# M1_DRV8301_driver.net
KiCad netlist of a schematic drawn in Altium Designer
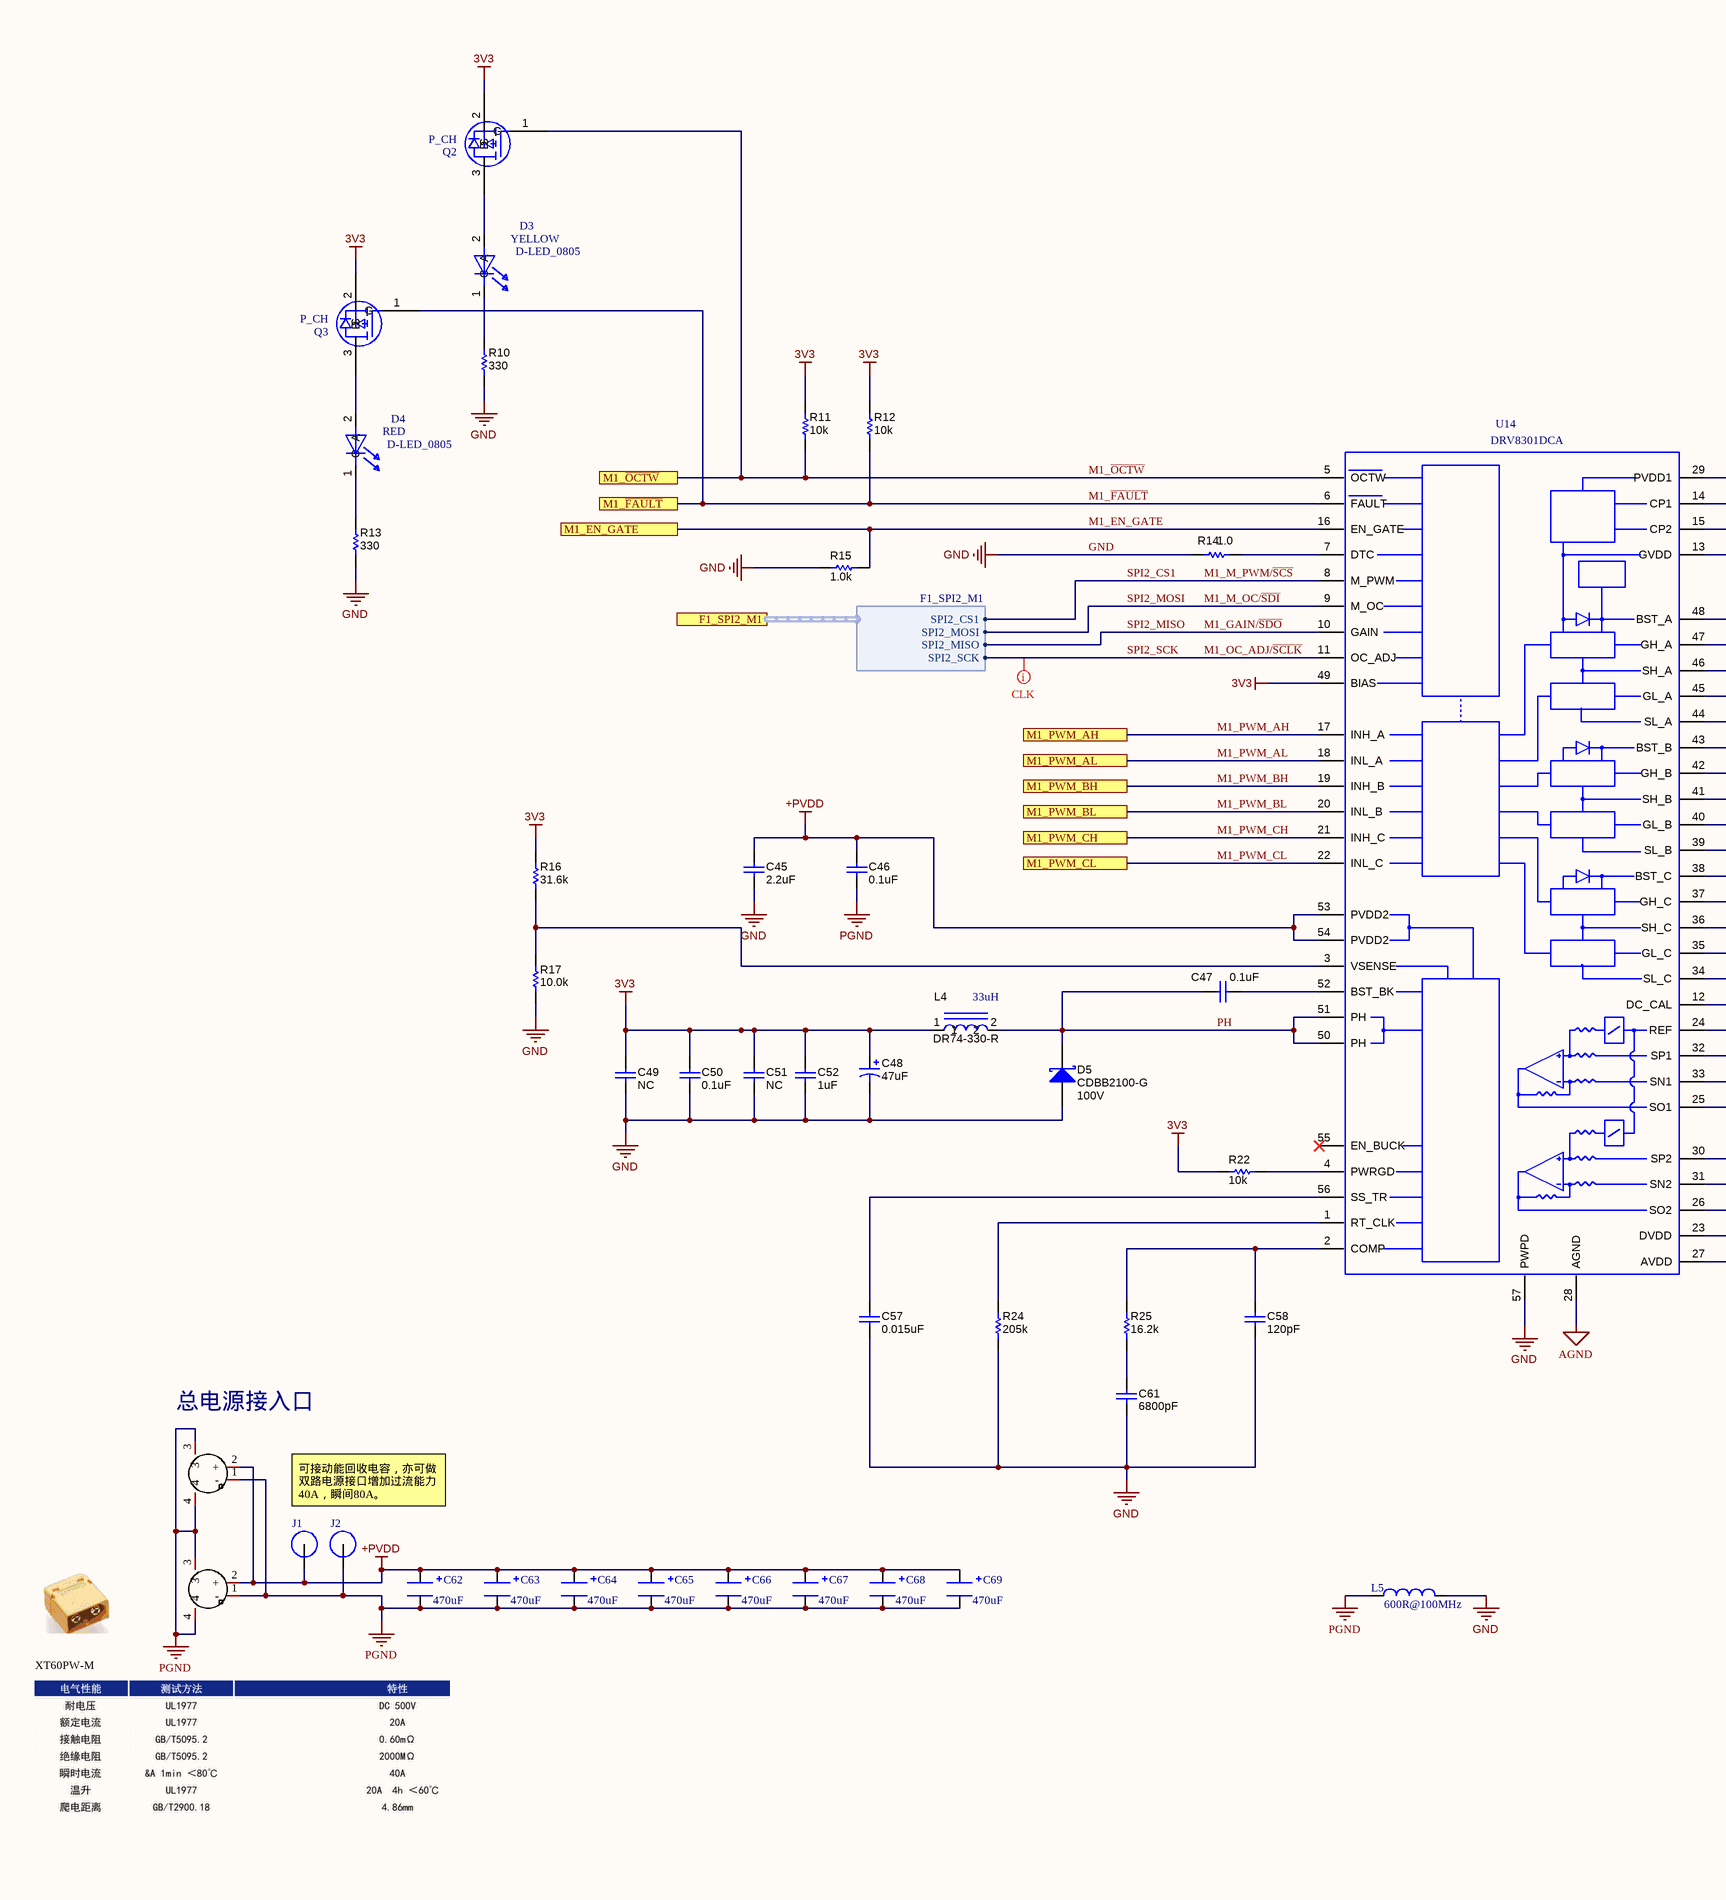
[diagram p0: M1_DRV8301_driver.SchDoc, left]
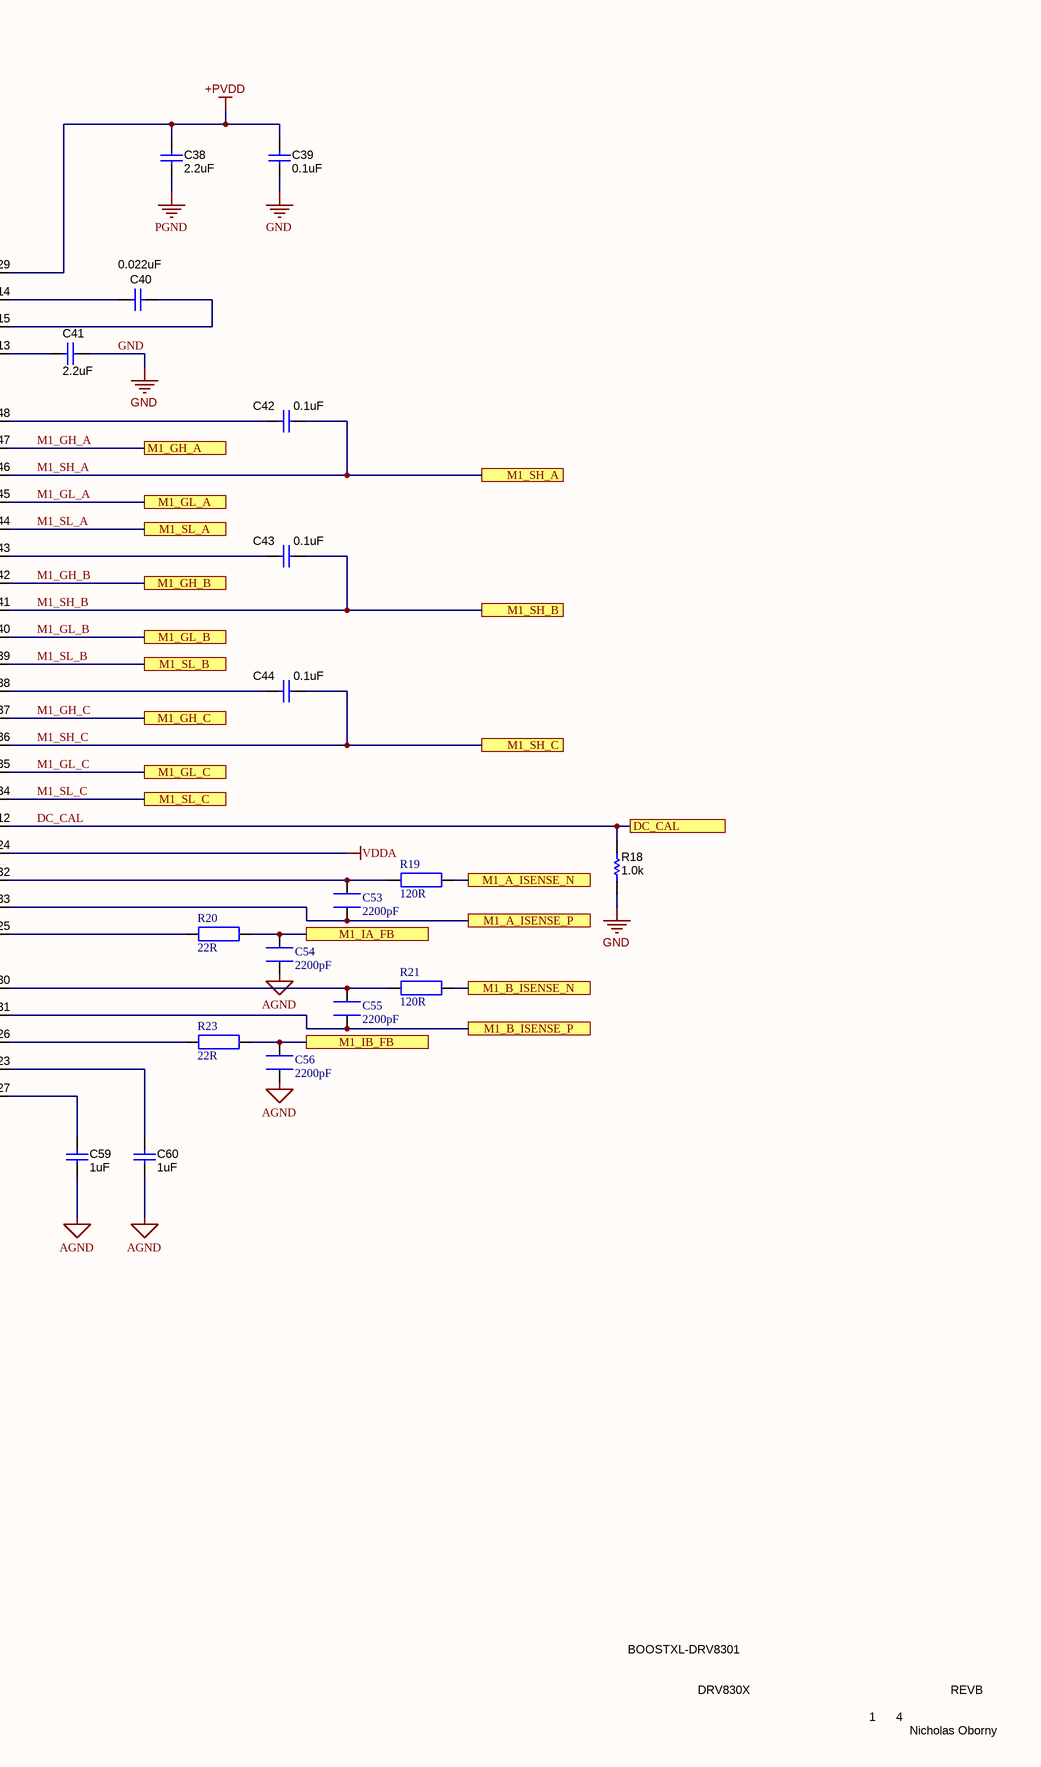
[diagram p1: M1_DRV8301_driver.SchDoc, right]

(export (version "E")
  (design (tool "Eeschema 10.0.6"))
  (components
    (comp (ref "C38")
      (value "GRM32ER72A225KA35L")
      (footprint "1210L")
      (description "CAP, CERM, 2.2uF, 100V, +/-10%, X7R, 1210")
      (fields
        (field (name "VALUEDISPLAYED") "2.2uF")
        (field (name "MANUFACTURER") "MuRata")
        (field (name "PUBLISHER") "Texas Instruments")
      )
      (libsource (lib "Capacitor_Ceramic") (part "GRM32ER72A225KA35L"))
    )
    (comp (ref "C39")
      (value "GRM188R72A104KA35D")
      (footprint "0603L")
      (description "CAP, CERM, 0.1uF, 100V, +/-10%, X7R, 0603")
      (fields
        (field (name "VALUEDISPLAYED") "0.1uF")
        (field (name "MANUFACTURER") "MuRata")
        (field (name "PUBLISHER") "Texas Instruments")
      )
      (libsource (lib "Capacitor_Ceramic") (part "GRM188R72A104KA35D"))
    )
    (comp (ref "C40")
      (value "C1608X7R1H223K")
      (footprint "0603L")
      (description "CAP, CERM, 0.022uF, 50V, +/-10%, X7R, 0603")
      (fields
        (field (name "VALUEDISPLAYED") "0.022uF")
        (field (name "MANUFACTURER") "TDK")
        (field (name "PUBLISHER") "Texas Instruments")
      )
      (libsource (lib "Capacitor_Ceramic") (part "C1608X7R1H223K"))
    )
    (comp (ref "C41")
      (value "GRM219R61E225KA12D")
      (footprint "0805L")
      (description "CAP, CERM, 2.2uF, 25V, +/-10%, X5R, 0805")
      (fields
        (field (name "VALUEDISPLAYED") "2.2uF")
        (field (name "MANUFACTURER") "MuRata")
        (field (name "PUBLISHER") "Texas Instruments")
      )
      (libsource (lib "Capacitor_Ceramic") (part "GRM219R61E225KA12D"))
    )
    (comp (ref "C42")
      (value "C1608X7R1H104K")
      (footprint "0603L")
      (description "CAP, CERM, 0.1uF, 50V, +/-10%, X7R, 0603")
      (fields
        (field (name "VALUEDISPLAYED") "0.1uF")
        (field (name "MANUFACTURER") "TDK")
        (field (name "PUBLISHER") "Texas Instruments")
      )
      (libsource (lib "Capacitor_Ceramic") (part "C1608X7R1H104K"))
    )
    (comp (ref "C43")
      (value "C1608X7R1H104K")
      (footprint "0603L")
      (description "CAP, CERM, 0.1uF, 50V, +/-10%, X7R, 0603")
      (fields
        (field (name "VALUEDISPLAYED") "0.1uF")
        (field (name "MANUFACTURER") "TDK")
        (field (name "PUBLISHER") "Texas Instruments")
      )
      (libsource (lib "Capacitor_Ceramic") (part "C1608X7R1H104K"))
    )
    (comp (ref "C44")
      (value "C1608X7R1H104K")
      (footprint "0603L")
      (description "CAP, CERM, 0.1uF, 50V, +/-10%, X7R, 0603")
      (fields
        (field (name "VALUEDISPLAYED") "0.1uF")
        (field (name "MANUFACTURER") "TDK")
        (field (name "PUBLISHER") "Texas Instruments")
      )
      (libsource (lib "Capacitor_Ceramic") (part "C1608X7R1H104K"))
    )
    (comp (ref "C45")
      (value "GRM32ER72A225KA35L")
      (footprint "1210L")
      (description "CAP, CERM, 2.2uF, 100V, +/-10%, X7R, 1210")
      (fields
        (field (name "VALUEDISPLAYED") "2.2uF")
        (field (name "MANUFACTURER") "MuRata")
        (field (name "PUBLISHER") "Texas Instruments")
      )
      (libsource (lib "Capacitor_Ceramic") (part "GRM32ER72A225KA35L"))
    )
    (comp (ref "C46")
      (value "GRM188R72A104KA35D")
      (footprint "0603L")
      (description "CAP, CERM, 0.1uF, 100V, +/-10%, X7R, 0603")
      (fields
        (field (name "VALUEDISPLAYED") "0.1uF")
        (field (name "MANUFACTURER") "MuRata")
        (field (name "PUBLISHER") "Texas Instruments")
      )
      (libsource (lib "Capacitor_Ceramic") (part "GRM188R72A104KA35D"))
    )
    (comp (ref "C47")
      (value "C1608X7R1H104K")
      (footprint "0603L")
      (description "CAP, CERM, 0.1uF, 50V, +/-10%, X7R, 0603")
      (fields
        (field (name "VALUEDISPLAYED") "0.1uF")
        (field (name "MANUFACTURER") "TDK")
        (field (name "PUBLISHER") "Texas Instruments")
      )
      (libsource (lib "Capacitor_Ceramic") (part "C1608X7R1H104K"))
    )
    (comp (ref "C48")
      (value "EEE-FK1E470P")
      (footprint "SM_RADIAL_D")
      (description "CAP, AL, 47uF, 25V, +/-20%, 0.36 ohm, SMD")
      (fields
        (field (name "VALUEDISPLAYED") "47uF")
        (field (name "MANUFACTURER") "Panasonic")
        (field (name "PUBLISHER") "Texas Instruments")
      )
      (libsource (lib "Capacitor_Aluminum") (part "EEE-FK1E470P"))
    )
    (comp (ref "C49")
      (value "C1608X7R1E104K")
      (footprint "0603L")
      (description "CAP, CERM, 0.1uF, 25V, +/-10%, X7R, 0603")
      (fields
        (field (name "VALUEDISPLAYED") "NC")
        (field (name "MANUFACTURER") "TDK")
        (field (name "PUBLISHER") "Texas Instruments")
      )
      (libsource (lib "Capacitor_Ceramic") (part "C1608X7R1E104K"))
    )
    (comp (ref "C50")
      (value "C1608X7R1E104K")
      (footprint "0603L")
      (description "CAP, CERM, 0.1uF, 25V, +/-10%, X7R, 0603")
      (fields
        (field (name "VALUEDISPLAYED") "0.1uF")
        (field (name "MANUFACTURER") "TDK")
        (field (name "PUBLISHER") "Texas Instruments")
      )
      (libsource (lib "Capacitor_Ceramic") (part "C1608X7R1E104K"))
    )
    (comp (ref "C51")
      (value "C1608X5R1E105K080AC")
      (footprint "0603L")
      (description "CAP, CERM, 1uF, 25V, +/-10%, X5R, 0603")
      (fields
        (field (name "VALUEDISPLAYED") "NC")
        (field (name "MANUFACTURER") "TDK")
        (field (name "PUBLISHER") "Texas Instruments")
      )
      (libsource (lib "Capacitor_Ceramic") (part "C1608X5R1E105K080AC"))
    )
    (comp (ref "C52")
      (value "C1608X5R1E105K080AC")
      (footprint "0603L")
      (description "CAP, CERM, 1uF, 25V, +/-10%, X5R, 0603")
      (fields
        (field (name "VALUEDISPLAYED") "1uF")
        (field (name "MANUFACTURER") "TDK")
        (field (name "PUBLISHER") "Texas Instruments")
      )
      (libsource (lib "Capacitor_Ceramic") (part "C1608X5R1E105K080AC"))
    )
    (comp (ref "C53")
      (value "2200pF")
      (footprint "CAPC1608X09L")
      (description "CAP CER 2200PF 50V NP0 0603")
      (fields
        (field (name "MANUFACTURER") "Murata Electronics North America")
        (field (name "TOLERANCE") "±5%")
      )
      (libsource (lib "CustomComponents") (part "GRM1885C1H222JA01D"))
    )
    (comp (ref "C54")
      (value "2200pF")
      (footprint "CAPC1608X09L")
      (description "CAP CER 2200PF 50V NP0 0603")
      (fields
        (field (name "MANUFACTURER") "Murata Electronics North America")
        (field (name "TOLERANCE") "±5%")
      )
      (libsource (lib "CustomComponents") (part "GRM1885C1H222JA01D"))
    )
    (comp (ref "C55")
      (value "2200pF")
      (footprint "CAPC1608X09L")
      (description "CAP CER 2200PF 50V NP0 0603")
      (fields
        (field (name "MANUFACTURER") "Murata Electronics North America")
        (field (name "TOLERANCE") "±5%")
      )
      (libsource (lib "CustomComponents") (part "GRM1885C1H222JA01D"))
    )
    (comp (ref "C56")
      (value "2200pF")
      (footprint "CAPC1608X09L")
      (description "CAP CER 2200PF 50V NP0 0603")
      (fields
        (field (name "MANUFACTURER") "Murata Electronics North America")
        (field (name "TOLERANCE") "±5%")
      )
      (libsource (lib "CustomComponents") (part "GRM1885C1H222JA01D"))
    )
    (comp (ref "C57")
      (value "GRM188R71H153KA01D")
      (footprint "0603L")
      (description "CAP, CERM, 0.015uF, 50V, +/-10%, X7R, 0603")
      (fields
        (field (name "VALUEDISPLAYED") "0.015uF")
        (field (name "MANUFACTURER") "MuRata")
        (field (name "PUBLISHER") "Texas Instruments")
      )
      (libsource (lib "Capacitor_Ceramic") (part "GRM188R71H153KA01D"))
    )
    (comp (ref "C58")
      (value "GRM1885C1H121JA01D")
      (footprint "0603L")
      (description "CAP, CERM, 120pF, 50V, +/-5%, C0G/NP0, 0603")
      (fields
        (field (name "VALUEDISPLAYED") "120pF")
        (field (name "MANUFACTURER") "MuRata")
        (field (name "PUBLISHER") "Texas Instruments")
      )
      (libsource (lib "Capacitor_Ceramic") (part "GRM1885C1H121JA01D"))
    )
    (comp (ref "C59")
      (value "GRM188R61E105KA12D")
      (footprint "0603L")
      (description "CAP, CERM, 1uF, 25V, +/-10%, X5R, 0603")
      (fields
        (field (name "VALUEDISPLAYED") "1uF")
        (field (name "MANUFACTURER") "MuRata")
        (field (name "PUBLISHER") "Texas Instruments")
      )
      (libsource (lib "Capacitor_Ceramic") (part "GRM188R61E105KA12D"))
    )
    (comp (ref "C60")
      (value "GRM188R61E105KA12D")
      (footprint "0603L")
      (description "CAP, CERM, 1uF, 25V, +/-10%, X5R, 0603")
      (fields
        (field (name "VALUEDISPLAYED") "1uF")
        (field (name "MANUFACTURER") "MuRata")
        (field (name "PUBLISHER") "Texas Instruments")
      )
      (libsource (lib "Capacitor_Ceramic") (part "GRM188R61E105KA12D"))
    )
    (comp (ref "C61")
      (value "GRM188R71H682KA01D")
      (footprint "0603L")
      (description "CAP, CERM, 6800pF, 50V, +/-10%, X7R, 0603")
      (fields
        (field (name "VALUEDISPLAYED") "6800pF")
        (field (name "MANUFACTURER") "MuRata")
        (field (name "PUBLISHER") "Texas Instruments")
      )
      (libsource (lib "Capacitor_Ceramic") (part "GRM188R71H682KA01D"))
    )
    (comp (ref "C62")
      (value "470uF")
      (footprint "CAP_ELEC_SIZE_G")
      (description "CAP, FP Series, 470 µF, 25 V, Radial Can - SMD, 10 mm")
      (fields
        (field (name "MANUFACTURER") "Panasonic Electronic Components")
        (field (name "TOLERANCE") "±20%")
      )
      (libsource (lib "CustomComponents") (part "EEEFP1E471AP"))
    )
    (comp (ref "C63")
      (value "470uF")
      (footprint "CAP_ELEC_SIZE_G")
      (description "CAP, FP Series, 470 µF, 25 V, Radial Can - SMD, 10 mm")
      (fields
        (field (name "MANUFACTURER") "Panasonic Electronic Components")
        (field (name "TOLERANCE") "±20%")
      )
      (libsource (lib "CustomComponents") (part "EEEFP1E471AP"))
    )
    (comp (ref "C64")
      (value "470uF")
      (footprint "CAP_ELEC_SIZE_G")
      (description "CAP, FP Series, 470 µF, 25 V, Radial Can - SMD, 10 mm")
      (fields
        (field (name "MANUFACTURER") "Panasonic Electronic Components")
        (field (name "TOLERANCE") "±20%")
      )
      (libsource (lib "CustomComponents") (part "EEEFP1E471AP"))
    )
    (comp (ref "C65")
      (value "470uF")
      (footprint "CAP_ELEC_SIZE_G")
      (description "CAP, FP Series, 470 µF, 25 V, Radial Can - SMD, 10 mm")
      (fields
        (field (name "MANUFACTURER") "Panasonic Electronic Components")
        (field (name "TOLERANCE") "±20%")
      )
      (libsource (lib "CustomComponents") (part "EEEFP1E471AP"))
    )
    (comp (ref "C66")
      (value "470uF")
      (footprint "CAP_ELEC_SIZE_G")
      (description "CAP, FP Series, 470 µF, 25 V, Radial Can - SMD, 10 mm")
      (fields
        (field (name "MANUFACTURER") "Panasonic Electronic Components")
        (field (name "TOLERANCE") "±20%")
      )
      (libsource (lib "CustomComponents") (part "EEEFP1E471AP"))
    )
    (comp (ref "C67")
      (value "470uF")
      (footprint "CAP_ELEC_SIZE_G")
      (description "CAP, FP Series, 470 µF, 25 V, Radial Can - SMD, 10 mm")
      (fields
        (field (name "MANUFACTURER") "Panasonic Electronic Components")
        (field (name "TOLERANCE") "±20%")
      )
      (libsource (lib "CustomComponents") (part "EEEFP1E471AP"))
    )
    (comp (ref "C68")
      (value "470uF")
      (footprint "CAP_ELEC_SIZE_G")
      (description "CAP, FP Series, 470 µF, 25 V, Radial Can - SMD, 10 mm")
      (fields
        (field (name "MANUFACTURER") "Panasonic Electronic Components")
        (field (name "TOLERANCE") "±20%")
      )
      (libsource (lib "CustomComponents") (part "EEEFP1E471AP"))
    )
    (comp (ref "C69")
      (value "470uF")
      (footprint "CAP_ELEC_SIZE_G")
      (description "CAP, FP Series, 470 µF, 25 V, Radial Can - SMD, 10 mm")
      (fields
        (field (name "MANUFACTURER") "Panasonic Electronic Components")
        (field (name "TOLERANCE") "±20%")
      )
      (libsource (lib "CustomComponents") (part "EEEFP1E471AP"))
    )
    (comp (ref "CN2")
      (value "XT60PW-M")
      (footprint "CONN-TH_XT60PW-M")
      (fields (field (name "MANUFACTURER") "AMASS(艾迈斯)"))
      (libsource (lib "two_ax_PCB") (part "XT60PW-M"))
    )
    (comp (ref "CN3")
      (value "XT60PW-M")
      (footprint "CONN-TH_XT60PW-M")
      (fields (field (name "MANUFACTURER") "AMASS(艾迈斯)"))
      (libsource (lib "two_ax_PCB") (part "XT60PW-M"))
    )
    (comp (ref "D3")
      (value "D-LED_0805")
      (footprint "LED_0805")
      (description "LED THIN 585NM YEL DIFF 0805 SMD")
      (fields
        (field (name "PARTNUMBER") "SML-LXT0805YW-TR")
        (field (name "ALTIUM_VALUE") "YELLOW")
        (field (name "MANUFACTURER") "Lumex Opto/Components Inc")
      )
      (libsource (lib "*") (part "D-LED_0805"))
    )
    (comp (ref "D4")
      (value "D-LED_0805")
      (footprint "LED_0805")
      (description "LED THIN660NM SUPRED DIFF0805SMD")
      (fields
        (field (name "PARTNUMBER") "SML-LXT0805SRW-TR")
        (field (name "ALTIUM_VALUE") "RED")
        (field (name "MANUFACTURER") "Lumex Opto/Components Inc")
      )
      (libsource (lib "*") (part "D-LED_0805"))
    )
    (comp (ref "D5")
      (value "CDBB2100-G")
      (footprint "SMB")
      (description "Diode, Schottky, 100V, 2A, SMB")
      (fields
        (field (name "ALTIUM_VALUE") "100V")
        (field (name "MANUFACTURER") "Comchip Technology")
        (field (name "PUBLISHER") "Texas Instruments")
      )
      (libsource (lib "Diode") (part "CDBC5100-G"))
    )
    (comp (ref "J1")
      (value "~")
      (footprint "M3 Spade Hole")
      (description "M3 Spade Terminal")
      (libsource (lib "CustomComponents") (part "M3 Spade Terminal"))
    )
    (comp (ref "J2")
      (value "~")
      (footprint "M3 Spade Hole")
      (description "M3 Spade Terminal")
      (libsource (lib "CustomComponents") (part "M3 Spade Terminal"))
    )
    (comp (ref "L4")
      (value "DR74-330-R")
      (footprint "IND_DR74")
      (description "INDUCTOR SHIELD PWR 33UH SMD")
      (fields (field (name "MANUFACTURER") "Cooper Bussmann") (field (name "ALTIUM_VALUE") "33uH"))
      (libsource (lib "PADSlegacy_Passive") (part "IND_DR74-XXX"))
    )
    (comp (ref "L5")
      (value "600R@100MHz")
      (footprint "L0603")
      (description "SMD Chip ferrite bead, 600R@100MHz +/-25%, 350mA, 500mohm DC, 0603, T=0.8mm")
      (fields
        (field (name "INTERNAL_PART_NUMBER") "MCD-00047")
        (field (name "MANUFACTURER_PART_NUMBER") "FCM1608KF-601T03")
        (field (name "PROVIDED_BY") "SUBCO")
      )
      (libsource (lib "MCD_PARTS_database") (part "BEAD"))
    )
    (comp (ref "Q2")
      (value "P_CH")
      (footprint "SOT-23")
      (description "MOSFET P-CH 8V 5.4A SOT23-3")
      (fields (field (name "PARTNUMBER") "SI2325DS-T1-E3") (field (name "MANUFACTURER") "Vishey Siliconix"))
      (libsource (lib "*") (part "TR_PFET_SOT23"))
    )
    (comp (ref "Q3")
      (value "P_CH")
      (footprint "SOT-23")
      (description "MOSFET P-CH 8V 5.4A SOT23-3")
      (fields (field (name "PARTNUMBER") "SI2325DS-T1-E3") (field (name "MANUFACTURER") "Vishey Siliconix"))
      (libsource (lib "*") (part "TR_PFET_SOT23"))
    )
    (comp (ref "R10")
      (value "330")
      (footprint "0603L")
      (description "RES, 330 ohm, 5%, 0.1W, 0603")
      (fields
        (field (name "PARTNUMBER") "CRCW0603330RJNEA")
        (field (name "MANUFACTURER") "Vishay-Dale")
        (field (name "PUBLISHER") "Texas Instruments")
      )
      (libsource (lib "Resistor_0603") (part "CRCW0603330RJNEA"))
    )
    (comp (ref "R11")
      (value "10k")
      (footprint "0603L")
      (description "RES, 10k ohm, 5%, 0.1W, 0603")
      (fields
        (field (name "PARTNUMBER") "CRCW060310K0JNEA")
        (field (name "MANUFACTURER") "Vishay-Dale")
        (field (name "PUBLISHER") "Texas Instruments")
      )
      (libsource (lib "Resistor_0603") (part "CRCW060310K0JNEA"))
    )
    (comp (ref "R12")
      (value "10k")
      (footprint "0603L")
      (description "RES, 10k ohm, 5%, 0.1W, 0603")
      (fields
        (field (name "PARTNUMBER") "CRCW060310K0JNEA")
        (field (name "MANUFACTURER") "Vishay-Dale")
        (field (name "PUBLISHER") "Texas Instruments")
      )
      (libsource (lib "Resistor_0603") (part "CRCW060310K0JNEA"))
    )
    (comp (ref "R13")
      (value "330")
      (footprint "0603L")
      (description "RES, 330 ohm, 5%, 0.1W, 0603")
      (fields
        (field (name "PARTNUMBER") "CRCW0603330RJNEA")
        (field (name "MANUFACTURER") "Vishay-Dale")
        (field (name "PUBLISHER") "Texas Instruments")
      )
      (libsource (lib "Resistor_0603") (part "CRCW0603330RJNEA"))
    )
    (comp (ref "R14")
      (value "1.0")
      (footprint "0603L")
      (description "RES, 1.0 ohm, 5%, 0.1W, 0603")
      (fields
        (field (name "PARTNUMBER") "CRCW06031R00JNEA")
        (field (name "MANUFACTURER") "Vishay-Dale")
        (field (name "PUBLISHER") "Texas Instruments")
      )
      (libsource (lib "Resistor_0603") (part "CRCW06031R00JNEA"))
    )
    (comp (ref "R15")
      (value "1.0k")
      (footprint "0603L")
      (description "RES, 1.0k ohm, 5%, 0.1W, 0603")
      (fields
        (field (name "PARTNUMBER") "CRCW06031K00JNEA")
        (field (name "MANUFACTURER") "Vishay-Dale")
        (field (name "PUBLISHER") "Texas Instruments")
      )
      (libsource (lib "Resistor_0603") (part "CRCW06031K00JNEA"))
    )
    (comp (ref "R16")
      (value "31.6k")
      (footprint "0603L")
      (description "RES, 31.6k ohm, 1%, 0.1W, 0603")
      (fields
        (field (name "PARTNUMBER") "CRCW060331K6FKEA")
        (field (name "MANUFACTURER") "Vishay-Dale")
        (field (name "PUBLISHER") "Texas Instruments")
      )
      (libsource (lib "Resistor_0603") (part "CRCW060331K6FKEA"))
    )
    (comp (ref "R17")
      (value "10.0k")
      (footprint "0603L")
      (description "RES, 10.0k ohm, 0.1%, 0.1W, 0603")
      (fields
        (field (name "PARTNUMBER") "RG1608P-103-B-T5")
        (field (name "MANUFACTURER") "Susumu Co Ltd")
        (field (name "PUBLISHER") "Texas Instruments")
      )
      (libsource (lib "Resistor_0603") (part "RG1608P-103-B-T5"))
    )
    (comp (ref "R18")
      (value "1.0k")
      (footprint "0603L")
      (description "RES, 1.0k ohm, 5%, 0.1W, 0603")
      (fields
        (field (name "PARTNUMBER") "CRCW06031K00JNEA")
        (field (name "MANUFACTURER") "Vishay-Dale")
        (field (name "PUBLISHER") "Texas Instruments")
      )
      (libsource (lib "Resistor_0603") (part "CRCW06031K00JNEA"))
    )
    (comp (ref "R19")
      (value "120R")
      (footprint "RESC1608X55N")
      (description "RES SMD 120 OHM 1% 1/10W 0603")
      (fields
        (field (name "MANUFACTURER") "Yageo")
        (field (name "MANUFACTURER PART NUMBER") "RC0603FR-07120RL")
      )
      (libsource (lib "CustomComponents") (part "RC0603FR-07120RL"))
    )
    (comp (ref "R20")
      (value "22R")
      (footprint "RESC1608X55N")
      (description "RES SMD 22 OHM 1% 1/10W 0603")
      (fields
        (field (name "MANUFACTURER") "Yageo")
        (field (name "MANUFACTURER PART NUMBER") "RC0603FR-0722RL")
      )
      (libsource (lib "CustomComponents") (part "RC0603FR-0722RL"))
    )
    (comp (ref "R21")
      (value "120R")
      (footprint "RESC1608X55N")
      (description "RES SMD 120 OHM 1% 1/10W 0603")
      (fields
        (field (name "MANUFACTURER") "Yageo")
        (field (name "MANUFACTURER PART NUMBER") "RC0603FR-07120RL")
      )
      (libsource (lib "CustomComponents") (part "RC0603FR-07120RL"))
    )
    (comp (ref "R22")
      (value "10k")
      (footprint "0603L")
      (description "RES, 10k ohm, 5%, 0.1W, 0603")
      (fields
        (field (name "PARTNUMBER") "CRCW060310K0JNEA")
        (field (name "MANUFACTURER") "Vishay-Dale")
        (field (name "PUBLISHER") "Texas Instruments")
      )
      (libsource (lib "Resistor_0603") (part "CRCW060310K0JNEA"))
    )
    (comp (ref "R23")
      (value "22R")
      (footprint "RESC1608X55N")
      (description "RES SMD 22 OHM 1% 1/10W 0603")
      (fields
        (field (name "MANUFACTURER") "Yageo")
        (field (name "MANUFACTURER PART NUMBER") "RC0603FR-0722RL")
      )
      (libsource (lib "CustomComponents") (part "RC0603FR-0722RL"))
    )
    (comp (ref "R24")
      (value "205k")
      (footprint "0603L")
      (description "RES, 205k ohm, 1%, 0.1W, 0603")
      (fields
        (field (name "PARTNUMBER") "CRCW0603205KFKEA")
        (field (name "MANUFACTURER") "Vishay-Dale")
        (field (name "PUBLISHER") "Texas Instruments")
      )
      (libsource (lib "Resistor_0603") (part "CRCW0603205KFKEA"))
    )
    (comp (ref "R25")
      (value "16.2k")
      (footprint "0603L")
      (description "RES, 16.2k ohm, 1%, 0.1W, 0603")
      (fields
        (field (name "PARTNUMBER") "CRCW060316K2FKEA")
        (field (name "MANUFACTURER") "Vishay-Dale")
        (field (name "PUBLISHER") "Texas Instruments")
      )
      (libsource (lib "Resistor_0603") (part "CRCW060316K2FKEA"))
    )
    (comp (ref "U14")
      (value "DRV8301DCA")
      (footprint "DCA_56P")
      (description "IC, 3 Phase Pre-Driver with Dual Current Shunt Amplifiers and Buck Regulator-Hardware Controlled")
      (fields (field (name "MANUFACTURER") "Texas Instruments") (field (name "VENDOR PART #") "Supplied"))
      (libsource (lib "*") (part "DRV8302DCA_ERIC"))
    )
  )
  (nets
    (net (code "2") (name "+PVDD") (class "Default")
      (node (ref "C38") (pin "1") (pinfunction "1_1") (pintype "passive"))
      (node (ref "C39") (pin "1") (pinfunction "1_1") (pintype "passive"))
      (node (ref "C45") (pin "1") (pinfunction "1_1") (pintype "passive"))
      (node (ref "C46") (pin "1") (pinfunction "1_1") (pintype "passive"))
      (node (ref "C62") (pin "1") (pinfunction "1_1") (pintype "passive"))
      (node (ref "C63") (pin "1") (pinfunction "1_1") (pintype "passive"))
      (node (ref "C64") (pin "1") (pinfunction "1_1") (pintype "passive"))
      (node (ref "C65") (pin "1") (pinfunction "1_1") (pintype "passive"))
      (node (ref "C66") (pin "1") (pinfunction "1_1") (pintype "passive"))
      (node (ref "C67") (pin "1") (pinfunction "1_1") (pintype "passive"))
      (node (ref "C68") (pin "1") (pinfunction "1_1") (pintype "passive"))
      (node (ref "C69") (pin "1") (pinfunction "1_1") (pintype "passive"))
      (node (ref "CN2") (pin "2") (pinfunction "+_2") (pintype "passive"))
      (node (ref "CN3") (pin "2") (pinfunction "+_2") (pintype "passive"))
      (node (ref "J1") (pin "1") (pinfunction "1_1") (pintype "passive"))
      (node (ref "U14") (pin "29") (pinfunction "PVDD1_29") (pintype "passive"))
      (node (ref "U14") (pin "53") (pinfunction "PVDD2_53") (pintype "passive"))
      (node (ref "U14") (pin "54") (pinfunction "PVDD2_54") (pintype "passive"))
    )
    (net (code "3") (name "/DC_CAL") (class "Default")
      (node (ref "R18") (pin "2") (pinfunction "2_2") (pintype "passive"))
      (node (ref "U14") (pin "12") (pinfunction "DC_CAL_12") (pintype "passive"))
    )
    (net (code "4") (name "/M1_A_ISENSE_N") (class "Default")
      (node (ref "R19") (pin "1") (pinfunction "0_1") (pintype "passive"))
    )
    (net (code "5") (name "/M1_A_ISENSE_P") (class "Default")
      (node (ref "C53") (pin "2") (pinfunction "2_2") (pintype "passive"))
      (node (ref "U14") (pin "33") (pinfunction "SN1_33") (pintype "passive"))
    )
    (net (code "6") (name "/M1_B_ISENSE_N") (class "Default")
      (node (ref "R21") (pin "1") (pinfunction "0_1") (pintype "passive"))
    )
    (net (code "7") (name "/M1_B_ISENSE_P") (class "Default")
      (node (ref "C55") (pin "2") (pinfunction "2_2") (pintype "passive"))
      (node (ref "U14") (pin "31") (pinfunction "SN2_31") (pintype "passive"))
    )
    (net (code "8") (name "/M1_EN_GATE") (class "Default")
      (node (ref "R15") (pin "2") (pinfunction "2_2") (pintype "passive"))
      (node (ref "U14") (pin "16") (pinfunction "EN_GATE_16") (pintype "passive"))
    )
    (net (code "9") (name "/M1_GAIN{slash}~{SDO}") (class "Default")
      (node (ref "U14") (pin "10") (pinfunction "GAIN_10") (pintype "passive"))
    )
    (net (code "10") (name "/M1_GH_A") (class "Default")
      (node (ref "U14") (pin "47") (pinfunction "GH_A_47") (pintype "passive"))
    )
    (net (code "11") (name "/M1_GH_B") (class "Default")
      (node (ref "U14") (pin "42") (pinfunction "GH_B_42") (pintype "passive"))
    )
    (net (code "12") (name "/M1_GH_C") (class "Default")
      (node (ref "U14") (pin "37") (pinfunction "GH_C_37") (pintype "passive"))
    )
    (net (code "13") (name "/M1_GL_A") (class "Default")
      (node (ref "U14") (pin "45") (pinfunction "GL_A_45") (pintype "passive"))
    )
    (net (code "14") (name "/M1_GL_B") (class "Default")
      (node (ref "U14") (pin "40") (pinfunction "GL_B_40") (pintype "passive"))
    )
    (net (code "15") (name "/M1_GL_C") (class "Default")
      (node (ref "U14") (pin "35") (pinfunction "GL_C_35") (pintype "passive"))
    )
    (net (code "16") (name "/M1_IA_FB") (class "Default")
      (node (ref "C54") (pin "1") (pinfunction "1_1") (pintype "passive"))
      (node (ref "R20") (pin "1") (pinfunction "0_1") (pintype "passive"))
    )
    (net (code "17") (name "/M1_IB_FB") (class "Default")
      (node (ref "C56") (pin "1") (pinfunction "1_1") (pintype "passive"))
      (node (ref "R23") (pin "1") (pinfunction "0_1") (pintype "passive"))
    )
    (net (code "18") (name "/M1_M_OC{slash}~{SDI}") (class "Default")
      (node (ref "U14") (pin "9") (pinfunction "M_OC_9") (pintype "passive"))
    )
    (net (code "19") (name "/M1_M_PWM{slash}~{SCS}") (class "Default")
      (node (ref "U14") (pin "8") (pinfunction "M_PWM_8") (pintype "passive"))
    )
    (net (code "20") (name "/M1_OC_ADJ{slash}~{SCLK}") (class "Default")
      (node (ref "U14") (pin "11") (pinfunction "OC_ADJ_11") (pintype "passive"))
    )
    (net (code "21") (name "/M1_PWM_AH") (class "Default")
      (node (ref "U14") (pin "17") (pinfunction "INH_A_17") (pintype "passive"))
    )
    (net (code "22") (name "/M1_PWM_AL") (class "Default")
      (node (ref "U14") (pin "18") (pinfunction "INL_A_18") (pintype "passive"))
    )
    (net (code "23") (name "/M1_PWM_BH") (class "Default")
      (node (ref "U14") (pin "19") (pinfunction "INH_B_19") (pintype "passive"))
    )
    (net (code "24") (name "/M1_PWM_BL") (class "Default")
      (node (ref "U14") (pin "20") (pinfunction "INL_B_20") (pintype "passive"))
    )
    (net (code "25") (name "/M1_PWM_CH") (class "Default")
      (node (ref "U14") (pin "21") (pinfunction "INH_C_21") (pintype "passive"))
    )
    (net (code "26") (name "/M1_PWM_CL") (class "Default")
      (node (ref "U14") (pin "22") (pinfunction "INL_C_22") (pintype "passive"))
    )
    (net (code "27") (name "/M1_SH_A") (class "Default")
      (node (ref "C42") (pin "2") (pinfunction "2_2") (pintype "passive"))
      (node (ref "U14") (pin "46") (pinfunction "SH_A_46") (pintype "passive"))
    )
    (net (code "28") (name "/M1_SH_B") (class "Default")
      (node (ref "C43") (pin "2") (pinfunction "2_2") (pintype "passive"))
      (node (ref "U14") (pin "41") (pinfunction "SH_B_41") (pintype "passive"))
    )
    (net (code "29") (name "/M1_SH_C") (class "Default")
      (node (ref "C44") (pin "2") (pinfunction "2_2") (pintype "passive"))
      (node (ref "U14") (pin "36") (pinfunction "SH_C_36") (pintype "passive"))
    )
    (net (code "30") (name "/M1_SL_A") (class "Default")
      (node (ref "U14") (pin "44") (pinfunction "SL_A_44") (pintype "passive"))
    )
    (net (code "31") (name "/M1_SL_B") (class "Default")
      (node (ref "U14") (pin "39") (pinfunction "SL_B_39") (pintype "passive"))
    )
    (net (code "32") (name "/M1_SL_C") (class "Default")
      (node (ref "U14") (pin "34") (pinfunction "SL_C_34") (pintype "passive"))
    )
    (net (code "33") (name "/M1_~{FAULT}") (class "Default")
      (node (ref "Q3") (pin "1") (pinfunction "G_1") (pintype "passive"))
      (node (ref "R12") (pin "1") (pinfunction "1_1") (pintype "passive"))
      (node (ref "U14") (pin "6") (pinfunction "FAULT_6") (pintype "passive"))
    )
    (net (code "34") (name "/M1_~{OCTW}") (class "Default")
      (node (ref "Q2") (pin "1") (pinfunction "G_1") (pintype "passive"))
      (node (ref "R11") (pin "1") (pinfunction "1_1") (pintype "passive"))
      (node (ref "U14") (pin "5") (pinfunction "OCTW_5") (pintype "passive"))
    )
    (net (code "35") (name "/PH") (class "Default")
      (node (ref "C47") (pin "1") (pinfunction "1_1") (pintype "passive"))
      (node (ref "D5") (pin "1") (pinfunction "K_1") (pintype "passive"))
      (node (ref "L4") (pin "2") (pinfunction "2_2") (pintype "passive"))
      (node (ref "U14") (pin "50") (pinfunction "PH_50") (pintype "passive"))
      (node (ref "U14") (pin "51") (pinfunction "PH_51") (pintype "passive"))
    )
    (net (code "37") (name "3V3") (class "Default")
      (node (ref "C48") (pin "1") (pinfunction "+_1") (pintype "passive"))
      (node (ref "C49") (pin "1") (pinfunction "1_1") (pintype "passive"))
      (node (ref "C50") (pin "1") (pinfunction "1_1") (pintype "passive"))
      (node (ref "C51") (pin "1") (pinfunction "1_1") (pintype "passive"))
      (node (ref "C52") (pin "1") (pinfunction "1_1") (pintype "passive"))
      (node (ref "L4") (pin "1") (pinfunction "1_1") (pintype "passive"))
      (node (ref "Q2") (pin "2") (pinfunction "S_2") (pintype "passive"))
      (node (ref "Q3") (pin "2") (pinfunction "S_2") (pintype "passive"))
      (node (ref "R11") (pin "2") (pinfunction "2_2") (pintype "passive"))
      (node (ref "R12") (pin "2") (pinfunction "2_2") (pintype "passive"))
      (node (ref "R16") (pin "2") (pinfunction "2_2") (pintype "passive"))
      (node (ref "R22") (pin "2") (pinfunction "2_2") (pintype "passive"))
      (node (ref "U14") (pin "49") (pinfunction "BIAS_49") (pintype "passive"))
    )
    (net (code "38") (name "AGND") (class "Default")
      (node (ref "C54") (pin "2") (pinfunction "2_2") (pintype "passive"))
      (node (ref "C56") (pin "2") (pinfunction "2_2") (pintype "passive"))
      (node (ref "C59") (pin "2") (pinfunction "2_2") (pintype "passive"))
      (node (ref "C60") (pin "2") (pinfunction "2_2") (pintype "passive"))
      (node (ref "U14") (pin "28") (pinfunction "AGND_28") (pintype "passive"))
    )
    (net (code "39") (name "GND") (class "Default")
      (node (ref "C39") (pin "2") (pinfunction "2_2") (pintype "passive"))
      (node (ref "C41") (pin "2") (pinfunction "2_2") (pintype "passive"))
      (node (ref "C45") (pin "2") (pinfunction "2_2") (pintype "passive"))
      (node (ref "C48") (pin "2") (pinfunction "-_2") (pintype "passive"))
      (node (ref "C49") (pin "2") (pinfunction "2_2") (pintype "passive"))
      (node (ref "C50") (pin "2") (pinfunction "2_2") (pintype "passive"))
      (node (ref "C51") (pin "2") (pinfunction "2_2") (pintype "passive"))
      (node (ref "C52") (pin "2") (pinfunction "2_2") (pintype "passive"))
      (node (ref "C57") (pin "2") (pinfunction "2_2") (pintype "passive"))
      (node (ref "C58") (pin "2") (pinfunction "2_2") (pintype "passive"))
      (node (ref "C61") (pin "2") (pinfunction "2_2") (pintype "passive"))
      (node (ref "D5") (pin "2") (pinfunction "A_2") (pintype "passive"))
      (node (ref "L5") (pin "2") (pinfunction "2_2") (pintype "passive"))
      (node (ref "R10") (pin "1") (pinfunction "1_1") (pintype "passive"))
      (node (ref "R13") (pin "1") (pinfunction "1_1") (pintype "passive"))
      (node (ref "R14") (pin "1") (pinfunction "1_1") (pintype "passive"))
      (node (ref "R15") (pin "1") (pinfunction "1_1") (pintype "passive"))
      (node (ref "R17") (pin "1") (pinfunction "1_1") (pintype "passive"))
      (node (ref "R18") (pin "1") (pinfunction "1_1") (pintype "passive"))
      (node (ref "R24") (pin "1") (pinfunction "1_1") (pintype "passive"))
      (node (ref "U14") (pin "57") (pinfunction "PWPD_57") (pintype "passive"))
    )
    (net (code "40") (name "Net-(C61-Pad1)") (class "Default")
      (node (ref "C61") (pin "1") (pinfunction "1_1") (pintype "passive"))
      (node (ref "R25") (pin "1") (pinfunction "1_1") (pintype "passive"))
    )
    (net (code "41") (name "Net-(D3-A)") (class "Default")
      (node (ref "D3") (pin "2") (pinfunction "A_2") (pintype "passive"))
      (node (ref "Q2") (pin "3") (pinfunction "D_3") (pintype "passive"))
    )
    (net (code "42") (name "Net-(D3-C)") (class "Default")
      (node (ref "D3") (pin "1") (pinfunction "C_1") (pintype "passive"))
      (node (ref "R10") (pin "2") (pinfunction "2_2") (pintype "passive"))
    )
    (net (code "43") (name "Net-(D4-A)") (class "Default")
      (node (ref "D4") (pin "2") (pinfunction "A_2") (pintype "passive"))
      (node (ref "Q3") (pin "3") (pinfunction "D_3") (pintype "passive"))
    )
    (net (code "44") (name "Net-(D4-C)") (class "Default")
      (node (ref "D4") (pin "1") (pinfunction "C_1") (pintype "passive"))
      (node (ref "R13") (pin "2") (pinfunction "2_2") (pintype "passive"))
    )
    (net (code "45") (name "Net-(U14-AVDD)") (class "Default")
      (node (ref "C59") (pin "1") (pinfunction "1_1") (pintype "passive"))
      (node (ref "U14") (pin "27") (pinfunction "AVDD_27") (pintype "passive"))
    )
    (net (code "46") (name "Net-(U14-BST_A)") (class "Default")
      (node (ref "C42") (pin "1") (pinfunction "1_1") (pintype "passive"))
      (node (ref "U14") (pin "48") (pinfunction "BST_A_48") (pintype "passive"))
    )
    (net (code "47") (name "Net-(U14-BST_B)") (class "Default")
      (node (ref "C43") (pin "1") (pinfunction "1_1") (pintype "passive"))
      (node (ref "U14") (pin "43") (pinfunction "BST_B_43") (pintype "passive"))
    )
    (net (code "48") (name "Net-(U14-BST_BK)") (class "Default")
      (node (ref "C47") (pin "2") (pinfunction "2_2") (pintype "passive"))
      (node (ref "U14") (pin "52") (pinfunction "BST_BK_52") (pintype "passive"))
    )
    (net (code "49") (name "Net-(U14-BST_C)") (class "Default")
      (node (ref "C44") (pin "1") (pinfunction "1_1") (pintype "passive"))
      (node (ref "U14") (pin "38") (pinfunction "BST_C_38") (pintype "passive"))
    )
    (net (code "50") (name "Net-(U14-COMP)") (class "Default")
      (node (ref "C58") (pin "1") (pinfunction "1_1") (pintype "passive"))
      (node (ref "R25") (pin "2") (pinfunction "2_2") (pintype "passive"))
      (node (ref "U14") (pin "2") (pinfunction "COMP_2") (pintype "passive"))
    )
    (net (code "51") (name "Net-(U14-CP1)") (class "Default")
      (node (ref "C40") (pin "1") (pinfunction "1_1") (pintype "passive"))
      (node (ref "U14") (pin "14") (pinfunction "CP1_14") (pintype "passive"))
    )
    (net (code "52") (name "Net-(U14-CP2)") (class "Default")
      (node (ref "C40") (pin "2") (pinfunction "2_2") (pintype "passive"))
      (node (ref "U14") (pin "15") (pinfunction "CP2_15") (pintype "passive"))
    )
    (net (code "53") (name "Net-(U14-DTC)") (class "Default")
      (node (ref "R14") (pin "2") (pinfunction "2_2") (pintype "passive"))
      (node (ref "U14") (pin "7") (pinfunction "DTC_7") (pintype "passive"))
    )
    (net (code "54") (name "Net-(U14-DVDD)") (class "Default")
      (node (ref "C60") (pin "1") (pinfunction "1_1") (pintype "passive"))
      (node (ref "U14") (pin "23") (pinfunction "DVDD_23") (pintype "passive"))
    )
    (net (code "55") (name "Net-(U14-GVDD)") (class "Default")
      (node (ref "C41") (pin "1") (pinfunction "1_1") (pintype "passive"))
      (node (ref "U14") (pin "13") (pinfunction "GVDD_13") (pintype "passive"))
    )
    (net (code "56") (name "Net-(U14-PWRGD)") (class "Default")
      (node (ref "R22") (pin "1") (pinfunction "1_1") (pintype "passive"))
      (node (ref "U14") (pin "4") (pinfunction "PWRGD_4") (pintype "passive"))
    )
    (net (code "57") (name "Net-(U14-RT_CLK)") (class "Default")
      (node (ref "R24") (pin "2") (pinfunction "2_2") (pintype "passive"))
      (node (ref "U14") (pin "1") (pinfunction "RT_CLK_1") (pintype "passive"))
    )
    (net (code "58") (name "Net-(U14-SO1)") (class "Default")
      (node (ref "R20") (pin "2") (pinfunction "0_2") (pintype "passive"))
      (node (ref "U14") (pin "25") (pinfunction "SO1_25") (pintype "passive"))
    )
    (net (code "59") (name "Net-(U14-SO2)") (class "Default")
      (node (ref "R23") (pin "2") (pinfunction "0_2") (pintype "passive"))
      (node (ref "U14") (pin "26") (pinfunction "SO2_26") (pintype "passive"))
    )
    (net (code "60") (name "Net-(U14-SP1)") (class "Default")
      (node (ref "C53") (pin "1") (pinfunction "1_1") (pintype "passive"))
      (node (ref "R19") (pin "2") (pinfunction "0_2") (pintype "passive"))
      (node (ref "U14") (pin "32") (pinfunction "SP1_32") (pintype "passive"))
    )
    (net (code "61") (name "Net-(U14-SP2)") (class "Default")
      (node (ref "C55") (pin "1") (pinfunction "1_1") (pintype "passive"))
      (node (ref "R21") (pin "2") (pinfunction "0_2") (pintype "passive"))
      (node (ref "U14") (pin "30") (pinfunction "SP2_30") (pintype "passive"))
    )
    (net (code "62") (name "Net-(U14-SS_TR)") (class "Default")
      (node (ref "C57") (pin "1") (pinfunction "1_1") (pintype "passive"))
      (node (ref "U14") (pin "56") (pinfunction "SS_TR_56") (pintype "passive"))
    )
    (net (code "63") (name "Net-(U14-VSENSE)") (class "Default")
      (node (ref "R16") (pin "1") (pinfunction "1_1") (pintype "passive"))
      (node (ref "R17") (pin "2") (pinfunction "2_2") (pintype "passive"))
      (node (ref "U14") (pin "3") (pinfunction "VSENSE_3") (pintype "passive"))
    )
    (net (code "64") (name "PGND") (class "Default")
      (node (ref "C38") (pin "2") (pinfunction "2_2") (pintype "passive"))
      (node (ref "C46") (pin "2") (pinfunction "2_2") (pintype "passive"))
      (node (ref "C62") (pin "2") (pinfunction "2_2") (pintype "passive"))
      (node (ref "C63") (pin "2") (pinfunction "2_2") (pintype "passive"))
      (node (ref "C64") (pin "2") (pinfunction "2_2") (pintype "passive"))
      (node (ref "C65") (pin "2") (pinfunction "2_2") (pintype "passive"))
      (node (ref "C66") (pin "2") (pinfunction "2_2") (pintype "passive"))
      (node (ref "C67") (pin "2") (pinfunction "2_2") (pintype "passive"))
      (node (ref "C68") (pin "2") (pinfunction "2_2") (pintype "passive"))
      (node (ref "C69") (pin "2") (pinfunction "2_2") (pintype "passive"))
      (node (ref "CN2") (pin "1") (pinfunction "-_1") (pintype "passive"))
      (node (ref "CN2") (pin "3") (pinfunction "3_3") (pintype "passive"))
      (node (ref "CN2") (pin "4") (pinfunction "4_4") (pintype "passive"))
      (node (ref "CN3") (pin "1") (pinfunction "-_1") (pintype "passive"))
      (node (ref "CN3") (pin "3") (pinfunction "3_3") (pintype "passive"))
      (node (ref "CN3") (pin "4") (pinfunction "4_4") (pintype "passive"))
      (node (ref "J2") (pin "1") (pinfunction "1_1") (pintype "passive"))
      (node (ref "L5") (pin "1") (pinfunction "1_1") (pintype "passive"))
    )
    (net (code "65") (name "VDDA") (class "Default")
      (node (ref "U14") (pin "24") (pinfunction "REF_24") (pintype "passive"))
    )
    (net (code "66") (name "unconnected-(U14-EN_BUCK-Pad55)") (class "Default")
      (node (ref "U14") (pin "55") (pinfunction "EN_BUCK_55") (pintype "passive+no_connect"))
    )
  )
)
